# power.net
KiCad netlist of a schematic drawn in Altium Designer
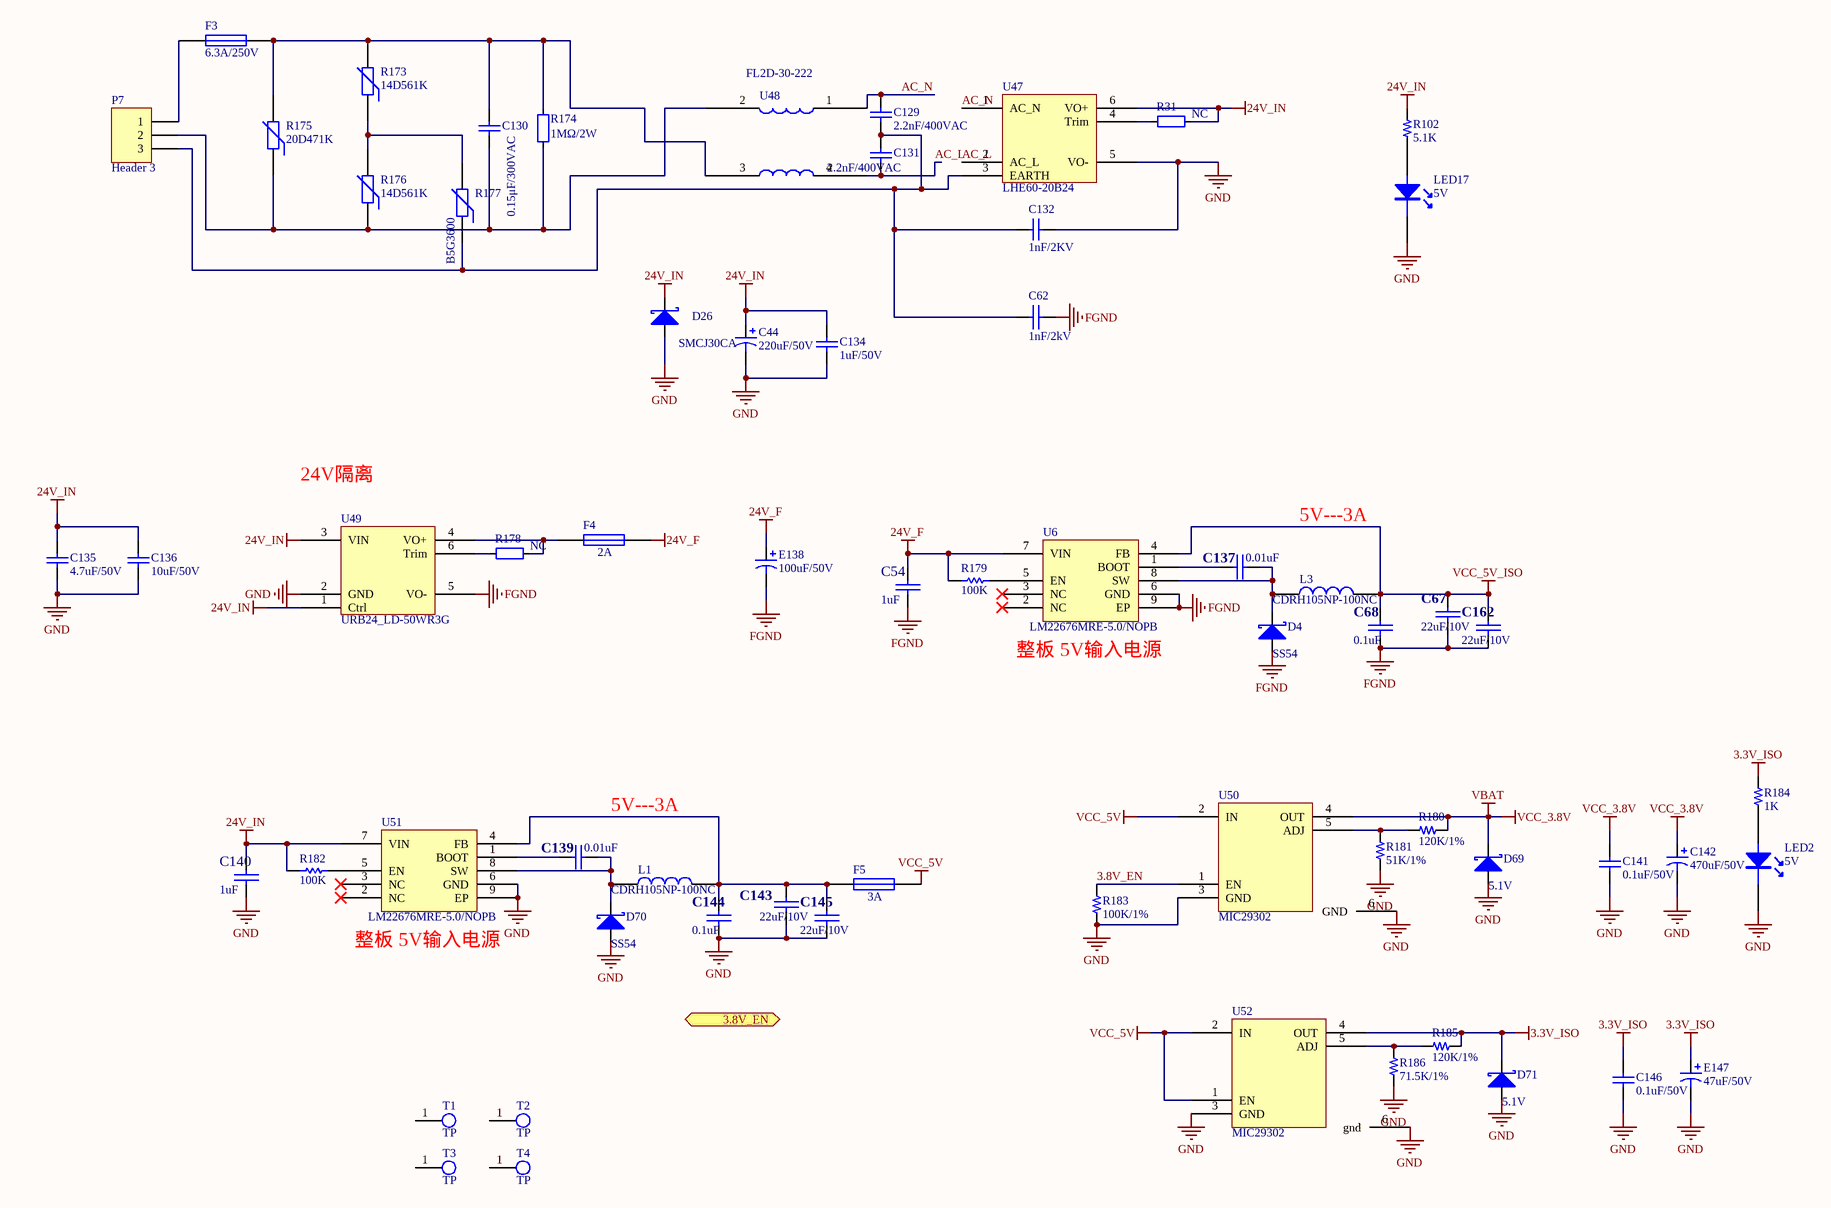
[diagram p0: power.SchDoc]

(export (version "E")
  (design (tool "Eeschema 10.0.6"))
  (components
    (comp (ref "C44")
      (value "220uF/50V")
      (footprint "Φ10×10")
      (description "Polarized Capacitor (Radial)")
      (fields (field (name "PUBLISHER") "Altium Limited"))
      (libsource (lib "Miscellaneous Devices") (part "Cap Pol1"))
    )
    (comp (ref "C54")
      (value "1uF")
      (footprint "0603C")
      (description "Capacitor")
      (libsource (lib "*") (part "CAP"))
    )
    (comp (ref "C62")
      (value "1nF/2kV")
      (footprint "1206C")
      (description "Capacitor")
      (libsource (lib "*") (part "CAP"))
    )
    (comp (ref "C67")
      (value "22uF/10V")
      (footprint "1210C")
      (description "Capacitor")
      (libsource (lib "*") (part "CAP"))
    )
    (comp (ref "C68")
      (value "0.1uF")
      (footprint "0603C")
      (description "Capacitor")
      (libsource (lib "*") (part "CAP"))
    )
    (comp (ref "C129")
      (value "2.2nF/400VAC")
      (footprint "15x18")
      (description "Capacitor")
      (fields (field (name "PUBLISHER") "Altium Limited"))
      (libsource (lib "Miscellaneous Devices") (part "Cap"))
    )
    (comp (ref "C130")
      (value "0.15μF/300VAC")
      (footprint "15x18")
      (description "Capacitor")
      (fields (field (name "PUBLISHER") "Altium Limited"))
      (libsource (lib "Miscellaneous Devices") (part "Cap"))
    )
    (comp (ref "C131")
      (value "2.2nF/400VAC")
      (footprint "15x18")
      (description "Capacitor")
      (fields (field (name "PUBLISHER") "Altium Limited"))
      (libsource (lib "Miscellaneous Devices") (part "Cap"))
    )
    (comp (ref "C132")
      (value "1nF/2KV")
      (footprint "1206C")
      (description "Capacitor")
      (fields (field (name "PUBLISHER") "Altium Limited"))
      (libsource (lib "Miscellaneous Devices") (part "Cap"))
    )
    (comp (ref "C134")
      (value "1uF/50V")
      (footprint "1210C")
      (description "Capacitor")
      (fields (field (name "PUBLISHER") "Altium Limited"))
      (libsource (lib "Miscellaneous Devices") (part "Cap"))
    )
    (comp (ref "C135")
      (value "4.7uF/50V")
      (footprint "1210C")
      (description "Capacitor")
      (fields (field (name "PUBLISHER") "Altium Limited"))
      (libsource (lib "Miscellaneous Devices") (part "Cap"))
    )
    (comp (ref "C136")
      (value "10uF/50V")
      (footprint "1210C")
      (description "Capacitor")
      (fields (field (name "PUBLISHER") "Altium Limited"))
      (libsource (lib "Miscellaneous Devices") (part "Cap"))
    )
    (comp (ref "C137")
      (value "0.01uF")
      (footprint "0603C")
      (description "Capacitor")
      (libsource (lib "*") (part "CAP"))
    )
    (comp (ref "C139")
      (value "0.01uF")
      (footprint "0603C")
      (description "Capacitor")
      (libsource (lib "*") (part "CAP"))
    )
    (comp (ref "C140")
      (value "1uF")
      (footprint "0603C")
      (description "Capacitor")
      (libsource (lib "*") (part "CAP"))
    )
    (comp (ref "C141")
      (value "0.1uF/50V")
      (footprint "0603C")
      (description "Capacitor")
      (fields (field (name "PUBLISHER") "Altium Limited"))
      (libsource (lib "Miscellaneous Devices") (part "Cap"))
    )
    (comp (ref "C142")
      (value "470uF/50V")
      (footprint "Φ10×10")
      (description "Polarized Capacitor (Radial)")
      (fields (field (name "PUBLISHER") "Altium Limited"))
      (libsource (lib "Miscellaneous Devices") (part "Cap Pol1"))
    )
    (comp (ref "C143")
      (value "22uF/10V")
      (footprint "1210C")
      (description "Capacitor")
      (libsource (lib "*") (part "CAP"))
    )
    (comp (ref "C144")
      (value "0.1uF")
      (footprint "0603C")
      (description "Capacitor")
      (libsource (lib "*") (part "CAP"))
    )
    (comp (ref "C145")
      (value "22uF/10V")
      (footprint "1210C")
      (description "Capacitor")
      (libsource (lib "*") (part "CAP"))
    )
    (comp (ref "C146")
      (value "0.1uF/50V")
      (footprint "0603C")
      (description "Capacitor")
      (fields (field (name "PUBLISHER") "Altium Limited"))
      (libsource (lib "Miscellaneous Devices") (part "Cap"))
    )
    (comp (ref "C162")
      (value "22uF/10V")
      (footprint "1210C")
      (description "Capacitor")
      (libsource (lib "*") (part "CAP"))
    )
    (comp (ref "D4")
      (value "SS54")
      (footprint "SMC")
      (description "Schottky Diode")
      (libsource (lib "*") (part "DIODE S"))
    )
    (comp (ref "D26")
      (value "SMCJ30CA")
      (footprint "SMC")
      (description "Schottky Diode")
      (libsource (lib "*") (part "DIODE S"))
    )
    (comp (ref "D69")
      (value "5.1V")
      (footprint "SMA")
      (description "Schottky Diode")
      (libsource (lib "*") (part "DIODE S"))
    )
    (comp (ref "D70")
      (value "SS54")
      (footprint "SMC")
      (description "Schottky Diode")
      (libsource (lib "*") (part "DIODE S"))
    )
    (comp (ref "D71")
      (value "5.1V")
      (footprint "SMA")
      (description "Schottky Diode")
      (libsource (lib "*") (part "DIODE S"))
    )
    (comp (ref "E138")
      (value "100uF/50V")
      (footprint "Φ10×10")
      (description "Polarized Capacitor (Radial)")
      (fields (field (name "PUBLISHER") "Altium Limited"))
      (libsource (lib "Miscellaneous Devices") (part "Cap Pol1"))
    )
    (comp (ref "E147")
      (value "47uF/50V")
      (footprint "Φ10×10")
      (description "Polarized Capacitor (Radial)")
      (fields (field (name "PUBLISHER") "Altium Limited"))
      (libsource (lib "Miscellaneous Devices") (part "Cap Pol1"))
    )
    (comp (ref "F3")
      (value "6.3A/250V")
      (footprint "可视开关电源保险丝座")
      (description "Fuse")
      (fields (field (name "PUBLISHER") "Altium Limited"))
      (libsource (lib "Miscellaneous Devices") (part "Fuse 1"))
    )
    (comp (ref "F4")
      (value "2A")
      (footprint "1812-F")
      (description "Fuse")
      (fields (field (name "PUBLISHER") "Altium Limited"))
      (libsource (lib "Miscellaneous Devices") (part "Fuse 1"))
    )
    (comp (ref "F5")
      (value "3A")
      (footprint "1812-F")
      (description "Fuse")
      (fields (field (name "PUBLISHER") "Altium Limited"))
      (libsource (lib "Miscellaneous Devices") (part "Fuse 1"))
    )
    (comp (ref "L1") (value "CDRH105NP-100NC") (footprint "CDRH105") (libsource (lib "*") (part "INDUCTOR")))
    (comp (ref "L3") (value "CDRH105NP-100NC") (footprint "CDRH105") (libsource (lib "*") (part "INDUCTOR")))
    (comp (ref "LED2") (value "5V") (footprint "0603LED") (libsource (lib "*") (part "LED")))
    (comp (ref "LED17") (value "5V") (footprint "0603LED") (libsource (lib "*") (part "LED")))
    (comp (ref "P7")
      (value "Header 3")
      (footprint "KF128V-3P")
      (description "Header, 3-Pin")
      (fields (field (name "PUBLISHER") "Altium Limited"))
      (libsource (lib "Miscellaneous Connectors") (part "Header 3"))
    )
    (comp (ref "R31") (value "NC") (footprint "0603r") (libsource (lib "RC_M_D_00") (part "RES0603")))
    (comp (ref "R102")
      (value "5.1K")
      (footprint "0603R")
      (description "R")
      (libsource (lib "JRJ_1") (part "R"))
    )
    (comp (ref "R173")
      (value "14D561K")
      (footprint "14D561K")
      (description "Varistor (Voltage-Sensitive Resistor)")
      (fields (field (name "PUBLISHER") "Altium Limited"))
      (libsource (lib "Miscellaneous Devices") (part "Res Varistor"))
    )
    (comp (ref "R174") (value "1MΩ/2W") (footprint "5x15.5") (libsource (lib "RC_M_D_00") (part "RES0603")))
    (comp (ref "R175")
      (value "20D471K")
      (footprint "20D471K")
      (description "Varistor (Voltage-Sensitive Resistor)")
      (fields (field (name "PUBLISHER") "Altium Limited"))
      (libsource (lib "Miscellaneous Devices") (part "Res Varistor"))
    )
    (comp (ref "R176")
      (value "14D561K")
      (footprint "14D561K")
      (description "Varistor (Voltage-Sensitive Resistor)")
      (fields (field (name "PUBLISHER") "Altium Limited"))
      (libsource (lib "Miscellaneous Devices") (part "Res Varistor"))
    )
    (comp (ref "R177")
      (value "B5G3600")
      (footprint "B5G3600")
      (description "Varistor (Voltage-Sensitive Resistor)")
      (fields (field (name "PUBLISHER") "Altium Limited"))
      (libsource (lib "Miscellaneous Devices") (part "Res Varistor"))
    )
    (comp (ref "R178") (value "NC") (footprint "0603r") (libsource (lib "RC_M_D_00") (part "RES0603")))
    (comp (ref "R179")
      (value "100K")
      (footprint "0603R")
      (description "Resistor")
      (fields (field (name "PUBLISHER") "Altium Limited"))
      (libsource (lib "Miscellaneous Devices") (part "Res1"))
    )
    (comp (ref "R180")
      (value "120K/1%")
      (footprint "0603R")
      (description "R")
      (libsource (lib "JRJ_1") (part "R"))
    )
    (comp (ref "R181")
      (value "51K/1%")
      (footprint "0603R")
      (description "R")
      (libsource (lib "JRJ_1") (part "R"))
    )
    (comp (ref "R182")
      (value "100K")
      (footprint "0603R")
      (description "Resistor")
      (fields (field (name "PUBLISHER") "Altium Limited"))
      (libsource (lib "Miscellaneous Devices") (part "Res1"))
    )
    (comp (ref "R183")
      (value "100K/1%")
      (footprint "0603R")
      (description "R")
      (libsource (lib "JRJ_1") (part "R"))
    )
    (comp (ref "R184")
      (value "1K")
      (footprint "0603R")
      (description "R")
      (libsource (lib "JRJ_1") (part "R"))
    )
    (comp (ref "R185")
      (value "120K/1%")
      (footprint "0603R")
      (description "R")
      (libsource (lib "JRJ_1") (part "R"))
    )
    (comp (ref "R186")
      (value "71.5K/1%")
      (footprint "0603R")
      (description "R")
      (libsource (lib "JRJ_1") (part "R"))
    )
    (comp (ref "T1") (value "TP") (footprint "m2.5") (libsource (lib "Schlib_20110825") (part "TP")))
    (comp (ref "T2") (value "TP") (footprint "m2.5") (libsource (lib "Schlib_20110825") (part "TP")))
    (comp (ref "T3") (value "TP") (footprint "m2.5") (libsource (lib "Schlib_20110825") (part "TP")))
    (comp (ref "T4") (value "TP") (footprint "m2.5") (libsource (lib "Schlib_20110825") (part "TP")))
    (comp (ref "U6")
      (value "LM22676MRE-5.0/NOPB")
      (footprint "SOP127P600X168_HS-8N")
      (libsource (lib "Schlib1") (part "LM22676MR-5.0"))
    )
    (comp (ref "U47")
      (value "LHE60-20B24")
      (footprint "LHE60-20B24")
      (libsource (lib "Schlib1") (part "LHE60-20B24"))
    )
    (comp (ref "U48")
      (value "FL2D-30-222")
      (footprint "TY-100P")
      (description "PCB mounting filters")
      (libsource (lib "power") (part "TY-100P"))
    )
    (comp (ref "U49")
      (value "URB24_LD-50WR3G")
      (footprint "URB24_LD-50WR3G")
      (libsource (lib "Schlib1") (part "URB24_LD-50WR3G"))
    )
    (comp (ref "U50")
      (value "MIC29302")
      (footprint "TO228P1435X457-6N")
      (libsource (lib "power") (part "MIC29302"))
    )
    (comp (ref "U51")
      (value "LM22676MRE-5.0/NOPB")
      (footprint "SOP127P600X168_HS-8N")
      (libsource (lib "Schlib1") (part "LM22676MR-5.0"))
    )
    (comp (ref "U52")
      (value "MIC29302")
      (footprint "TO228P1435X457-6N")
      (libsource (lib "power") (part "MIC29302"))
    )
  )
  (nets
    (net (code "1") (name "/3.8V_EN") (class "Default")
      (node (ref "R183") (pin "2") (pintype "passive"))
      (node (ref "U50") (pin "1") (pinfunction "EN_1") (pintype "passive"))
    )
    (net (code "2") (name "/AC_L") (class "Default")
      (node (ref "C131") (pin "1") (pinfunction "1_1") (pintype "passive"))
      (node (ref "U47") (pin "2") (pinfunction "AC_L_2") (pintype "passive"))
      (node (ref "U48") (pin "4") (pintype "passive"))
    )
    (net (code "3") (name "/AC_N") (class "Default")
      (node (ref "C129") (pin "2") (pinfunction "2_2") (pintype "passive"))
      (node (ref "U47") (pin "1") (pinfunction "AC_N_1") (pintype "passive"))
      (node (ref "U48") (pin "1") (pinfunction "L_1") (pintype "passive"))
    )
    (net (code "4") (name "3.3V_ISO") (class "Default")
      (node (ref "C146") (pin "2") (pinfunction "2_2") (pintype "passive"))
      (node (ref "D71") (pin "2") (pinfunction "K_2") (pintype "passive"))
      (node (ref "E147") (pin "1") (pinfunction "1_1") (pintype "passive"))
      (node (ref "R184") (pin "2") (pintype "passive"))
      (node (ref "R185") (pin "1") (pintype "passive"))
      (node (ref "U52") (pin "4") (pinfunction "OUT_4") (pintype "passive"))
    )
    (net (code "5") (name "24V_F") (class "Default")
      (node (ref "C54") (pin "2") (pinfunction "2_2") (pintype "passive"))
      (node (ref "E138") (pin "1") (pinfunction "1_1") (pintype "passive"))
      (node (ref "F4") (pin "2") (pinfunction "2_2") (pintype "passive"))
      (node (ref "R179") (pin "2") (pinfunction "2_2") (pintype "passive"))
      (node (ref "U6") (pin "7") (pinfunction "VIN_7") (pintype "passive"))
    )
    (net (code "6") (name "24V_IN") (class "Default")
      (node (ref "C134") (pin "2") (pinfunction "2_2") (pintype "passive"))
      (node (ref "C135") (pin "2") (pinfunction "2_2") (pintype "passive"))
      (node (ref "C136") (pin "2") (pinfunction "2_2") (pintype "passive"))
      (node (ref "C140") (pin "2") (pinfunction "2_2") (pintype "passive"))
      (node (ref "C44") (pin "1") (pinfunction "1_1") (pintype "passive"))
      (node (ref "D26") (pin "2") (pinfunction "K_2") (pintype "passive"))
      (node (ref "R102") (pin "2") (pintype "passive"))
      (node (ref "R182") (pin "2") (pinfunction "2_2") (pintype "passive"))
      (node (ref "R31") (pin "2") (pinfunction "2_2") (pintype "passive"))
      (node (ref "U47") (pin "6") (pinfunction "VO+_6") (pintype "passive"))
      (node (ref "U49") (pin "1") (pinfunction "Ctrl_1") (pintype "passive"))
      (node (ref "U49") (pin "3") (pinfunction "VIN_3") (pintype "passive"))
      (node (ref "U51") (pin "7") (pinfunction "VIN_7") (pintype "passive"))
    )
    (net (code "7") (name "FGND") (class "Default")
      (node (ref "C162") (pin "2") (pinfunction "2_2") (pintype "passive"))
      (node (ref "C54") (pin "1") (pinfunction "1_1") (pintype "passive"))
      (node (ref "C62") (pin "1") (pinfunction "1_1") (pintype "passive"))
      (node (ref "C67") (pin "2") (pinfunction "2_2") (pintype "passive"))
      (node (ref "C68") (pin "2") (pinfunction "2_2") (pintype "passive"))
      (node (ref "D4") (pin "1") (pinfunction "A_1") (pintype "passive"))
      (node (ref "E138") (pin "2") (pinfunction "2_2") (pintype "passive"))
      (node (ref "U49") (pin "5") (pinfunction "VO-_5") (pintype "passive"))
      (node (ref "U6") (pin "6") (pinfunction "GND_6") (pintype "passive"))
      (node (ref "U6") (pin "9") (pinfunction "EP_9") (pintype "passive"))
    )
    (net (code "8") (name "GND") (class "Default")
      (node (ref "C132") (pin "1") (pinfunction "1_1") (pintype "passive"))
      (node (ref "C134") (pin "1") (pinfunction "1_1") (pintype "passive"))
      (node (ref "C135") (pin "1") (pinfunction "1_1") (pintype "passive"))
      (node (ref "C136") (pin "1") (pinfunction "1_1") (pintype "passive"))
      (node (ref "C140") (pin "1") (pinfunction "1_1") (pintype "passive"))
      (node (ref "C141") (pin "1") (pinfunction "1_1") (pintype "passive"))
      (node (ref "C142") (pin "2") (pinfunction "2_2") (pintype "passive"))
      (node (ref "C143") (pin "2") (pinfunction "2_2") (pintype "passive"))
      (node (ref "C144") (pin "2") (pinfunction "2_2") (pintype "passive"))
      (node (ref "C145") (pin "2") (pinfunction "2_2") (pintype "passive"))
      (node (ref "C146") (pin "1") (pinfunction "1_1") (pintype "passive"))
      (node (ref "C44") (pin "2") (pinfunction "2_2") (pintype "passive"))
      (node (ref "D26") (pin "1") (pinfunction "A_1") (pintype "passive"))
      (node (ref "D69") (pin "1") (pinfunction "A_1") (pintype "passive"))
      (node (ref "D70") (pin "1") (pinfunction "A_1") (pintype "passive"))
      (node (ref "D71") (pin "1") (pinfunction "A_1") (pintype "passive"))
      (node (ref "E147") (pin "2") (pinfunction "2_2") (pintype "passive"))
      (node (ref "LED17") (pin "2") (pinfunction "2_2") (pintype "passive"))
      (node (ref "LED2") (pin "2") (pinfunction "2_2") (pintype "passive"))
      (node (ref "R181") (pin "1") (pintype "passive"))
      (node (ref "R183") (pin "1") (pintype "passive"))
      (node (ref "R186") (pin "1") (pintype "passive"))
      (node (ref "U47") (pin "5") (pinfunction "VO-_5") (pintype "passive"))
      (node (ref "U49") (pin "2") (pinfunction "GND_2") (pintype "passive"))
      (node (ref "U50") (pin "3") (pinfunction "GND_3") (pintype "passive"))
      (node (ref "U50") (pin "6") (pinfunction "gnd_6") (pintype "passive"))
      (node (ref "U51") (pin "6") (pinfunction "GND_6") (pintype "passive"))
      (node (ref "U51") (pin "9") (pinfunction "EP_9") (pintype "passive"))
      (node (ref "U52") (pin "3") (pinfunction "GND_3") (pintype "passive"))
      (node (ref "U52") (pin "6") (pinfunction "gnd_6") (pintype "passive"))
    )
    (net (code "9") (name "Net-(C130-Pad1)") (class "Default")
      (node (ref "C130") (pin "1") (pinfunction "1_1") (pintype "passive"))
      (node (ref "P7") (pin "2") (pinfunction "2_2") (pintype "passive"))
      (node (ref "R174") (pin "2") (pinfunction "2_2") (pintype "passive"))
      (node (ref "R175") (pin "1") (pinfunction "1_1") (pintype "passive"))
      (node (ref "R176") (pin "1") (pinfunction "1_1") (pintype "passive"))
      (node (ref "U48") (pin "2") (pinfunction "L_2") (pintype "passive"))
    )
    (net (code "10") (name "Net-(C130-Pad2)") (class "Default")
      (node (ref "C130") (pin "2") (pinfunction "2_2") (pintype "passive"))
      (node (ref "F3") (pin "2") (pinfunction "2_2") (pintype "passive"))
      (node (ref "R173") (pin "2") (pinfunction "2_2") (pintype "passive"))
      (node (ref "R174") (pin "1") (pinfunction "1_1") (pintype "passive"))
      (node (ref "R175") (pin "2") (pinfunction "2_2") (pintype "passive"))
      (node (ref "U48") (pin "3") (pinfunction "L_3") (pintype "passive"))
    )
    (net (code "11") (name "Net-(D4-K)") (class "Default")
      (node (ref "C137") (pin "1") (pinfunction "1_1") (pintype "passive"))
      (node (ref "D4") (pin "2") (pinfunction "K_2") (pintype "passive"))
      (node (ref "L3") (pin "1") (pinfunction "1_1") (pintype "passive"))
      (node (ref "U6") (pin "8") (pinfunction "SW_8") (pintype "passive"))
    )
    (net (code "12") (name "Net-(D70-K)") (class "Default")
      (node (ref "C139") (pin "1") (pinfunction "1_1") (pintype "passive"))
      (node (ref "D70") (pin "2") (pinfunction "K_2") (pintype "passive"))
      (node (ref "L1") (pin "1") (pinfunction "1_1") (pintype "passive"))
      (node (ref "U51") (pin "8") (pinfunction "SW_8") (pintype "passive"))
    )
    (net (code "13") (name "Net-(F3-Pad1)") (class "Default")
      (node (ref "F3") (pin "1") (pinfunction "1_1") (pintype "passive"))
      (node (ref "P7") (pin "1") (pinfunction "1_1") (pintype "passive"))
    )
    (net (code "14") (name "Net-(LED2-Pad1)") (class "Default")
      (node (ref "LED2") (pin "1") (pinfunction "1_1") (pintype "passive"))
      (node (ref "R184") (pin "1") (pintype "passive"))
    )
    (net (code "15") (name "Net-(LED17-Pad1)") (class "Default")
      (node (ref "LED17") (pin "1") (pinfunction "1_1") (pintype "passive"))
      (node (ref "R102") (pin "1") (pintype "passive"))
    )
    (net (code "16") (name "Net-(R173-Pad1)") (class "Default")
      (node (ref "R173") (pin "1") (pinfunction "1_1") (pintype "passive"))
      (node (ref "R176") (pin "2") (pinfunction "2_2") (pintype "passive"))
      (node (ref "R177") (pin "2") (pinfunction "2_2") (pintype "passive"))
    )
    (net (code "17") (name "Net-(U6-BOOT)") (class "Default")
      (node (ref "C137") (pin "2") (pinfunction "2_2") (pintype "passive"))
      (node (ref "U6") (pin "1") (pinfunction "BOOT_1") (pintype "passive"))
    )
    (net (code "18") (name "Net-(U6-EN)") (class "Default")
      (node (ref "R179") (pin "1") (pinfunction "1_1") (pintype "passive"))
      (node (ref "U6") (pin "5") (pinfunction "EN_5") (pintype "passive"))
    )
    (net (code "19") (name "Net-(U47-EARTH)") (class "Default")
      (node (ref "C129") (pin "1") (pinfunction "1_1") (pintype "passive"))
      (node (ref "C131") (pin "2") (pinfunction "2_2") (pintype "passive"))
      (node (ref "C132") (pin "2") (pinfunction "2_2") (pintype "passive"))
      (node (ref "C62") (pin "2") (pinfunction "2_2") (pintype "passive"))
      (node (ref "P7") (pin "3") (pinfunction "3_3") (pintype "passive"))
      (node (ref "R177") (pin "1") (pinfunction "1_1") (pintype "passive"))
      (node (ref "U47") (pin "3") (pinfunction "EARTH_3") (pintype "passive"))
    )
    (net (code "20") (name "Net-(U47-Trim)") (class "Default")
      (node (ref "R31") (pin "1") (pinfunction "1_1") (pintype "passive"))
      (node (ref "U47") (pin "4") (pinfunction "Trim_4") (pintype "passive"))
    )
    (net (code "21") (name "Net-(U49-Trim)") (class "Default")
      (node (ref "R178") (pin "1") (pinfunction "1_1") (pintype "passive"))
      (node (ref "U49") (pin "6") (pinfunction "Trim_6") (pintype "passive"))
    )
    (net (code "22") (name "Net-(U49-VO+)") (class "Default")
      (node (ref "F4") (pin "1") (pinfunction "1_1") (pintype "passive"))
      (node (ref "R178") (pin "2") (pinfunction "2_2") (pintype "passive"))
      (node (ref "U49") (pin "4") (pinfunction "VO+_4") (pintype "passive"))
    )
    (net (code "23") (name "Net-(U50-ADJ)") (class "Default")
      (node (ref "R180") (pin "2") (pintype "passive"))
      (node (ref "R181") (pin "2") (pintype "passive"))
      (node (ref "U50") (pin "5") (pinfunction "ADJ_5") (pintype "passive"))
    )
    (net (code "24") (name "Net-(U51-BOOT)") (class "Default")
      (node (ref "C139") (pin "2") (pinfunction "2_2") (pintype "passive"))
      (node (ref "U51") (pin "1") (pinfunction "BOOT_1") (pintype "passive"))
    )
    (net (code "25") (name "Net-(U51-EN)") (class "Default")
      (node (ref "R182") (pin "1") (pinfunction "1_1") (pintype "passive"))
      (node (ref "U51") (pin "5") (pinfunction "EN_5") (pintype "passive"))
    )
    (net (code "26") (name "Net-(U51-FB)") (class "Default")
      (node (ref "C143") (pin "1") (pinfunction "1_1") (pintype "passive"))
      (node (ref "C144") (pin "1") (pinfunction "1_1") (pintype "passive"))
      (node (ref "C145") (pin "1") (pinfunction "1_1") (pintype "passive"))
      (node (ref "F5") (pin "1") (pinfunction "1_1") (pintype "passive"))
      (node (ref "L1") (pin "2") (pinfunction "2_2") (pintype "passive"))
      (node (ref "U51") (pin "4") (pinfunction "FB_4") (pintype "passive"))
    )
    (net (code "27") (name "Net-(U52-ADJ)") (class "Default")
      (node (ref "R185") (pin "2") (pintype "passive"))
      (node (ref "R186") (pin "2") (pintype "passive"))
      (node (ref "U52") (pin "5") (pinfunction "ADJ_5") (pintype "passive"))
    )
    (net (code "28") (name "VBAT") (class "Default")
      (node (ref "C141") (pin "2") (pinfunction "2_2") (pintype "passive"))
      (node (ref "C142") (pin "1") (pinfunction "1_1") (pintype "passive"))
      (node (ref "D69") (pin "2") (pinfunction "K_2") (pintype "passive"))
      (node (ref "R180") (pin "1") (pintype "passive"))
      (node (ref "U50") (pin "4") (pinfunction "OUT_4") (pintype "passive"))
    )
    (net (code "29") (name "VCC_5V") (class "Default")
      (node (ref "F5") (pin "2") (pinfunction "2_2") (pintype "passive"))
      (node (ref "U50") (pin "2") (pinfunction "IN_2") (pintype "passive"))
      (node (ref "U52") (pin "1") (pinfunction "EN_1") (pintype "passive"))
      (node (ref "U52") (pin "2") (pinfunction "IN_2") (pintype "passive"))
    )
    (net (code "30") (name "VCC_5V_ISO") (class "Default")
      (node (ref "C162") (pin "1") (pinfunction "1_1") (pintype "passive"))
      (node (ref "C67") (pin "1") (pinfunction "1_1") (pintype "passive"))
      (node (ref "C68") (pin "1") (pinfunction "1_1") (pintype "passive"))
      (node (ref "L3") (pin "2") (pinfunction "2_2") (pintype "passive"))
      (node (ref "U6") (pin "4") (pinfunction "FB_4") (pintype "passive"))
    )
    (net (code "31") (name "unconnected-(T1-Pad1)") (class "Default")
      (node (ref "T1") (pin "1") (pintype "passive"))
    )
    (net (code "32") (name "unconnected-(T2-Pad1)") (class "Default")
      (node (ref "T2") (pin "1") (pintype "passive"))
    )
    (net (code "33") (name "unconnected-(T3-Pad1)") (class "Default")
      (node (ref "T3") (pin "1") (pintype "passive"))
    )
    (net (code "34") (name "unconnected-(T4-Pad1)") (class "Default")
      (node (ref "T4") (pin "1") (pintype "passive"))
    )
    (net (code "35") (name "unconnected-(U6-NC-Pad2)") (class "Default")
      (node (ref "U6") (pin "2") (pinfunction "NC_2") (pintype "passive+no_connect"))
    )
    (net (code "36") (name "unconnected-(U6-NC-Pad3)") (class "Default")
      (node (ref "U6") (pin "3") (pinfunction "NC_3") (pintype "passive+no_connect"))
    )
    (net (code "37") (name "unconnected-(U51-NC-Pad2)") (class "Default")
      (node (ref "U51") (pin "2") (pinfunction "NC_2") (pintype "passive+no_connect"))
    )
    (net (code "38") (name "unconnected-(U51-NC-Pad3)") (class "Default")
      (node (ref "U51") (pin "3") (pinfunction "NC_3") (pintype "passive+no_connect"))
    )
  )
)
